# radio103.net
KiCad netlist of a schematic drawn in EAGLE
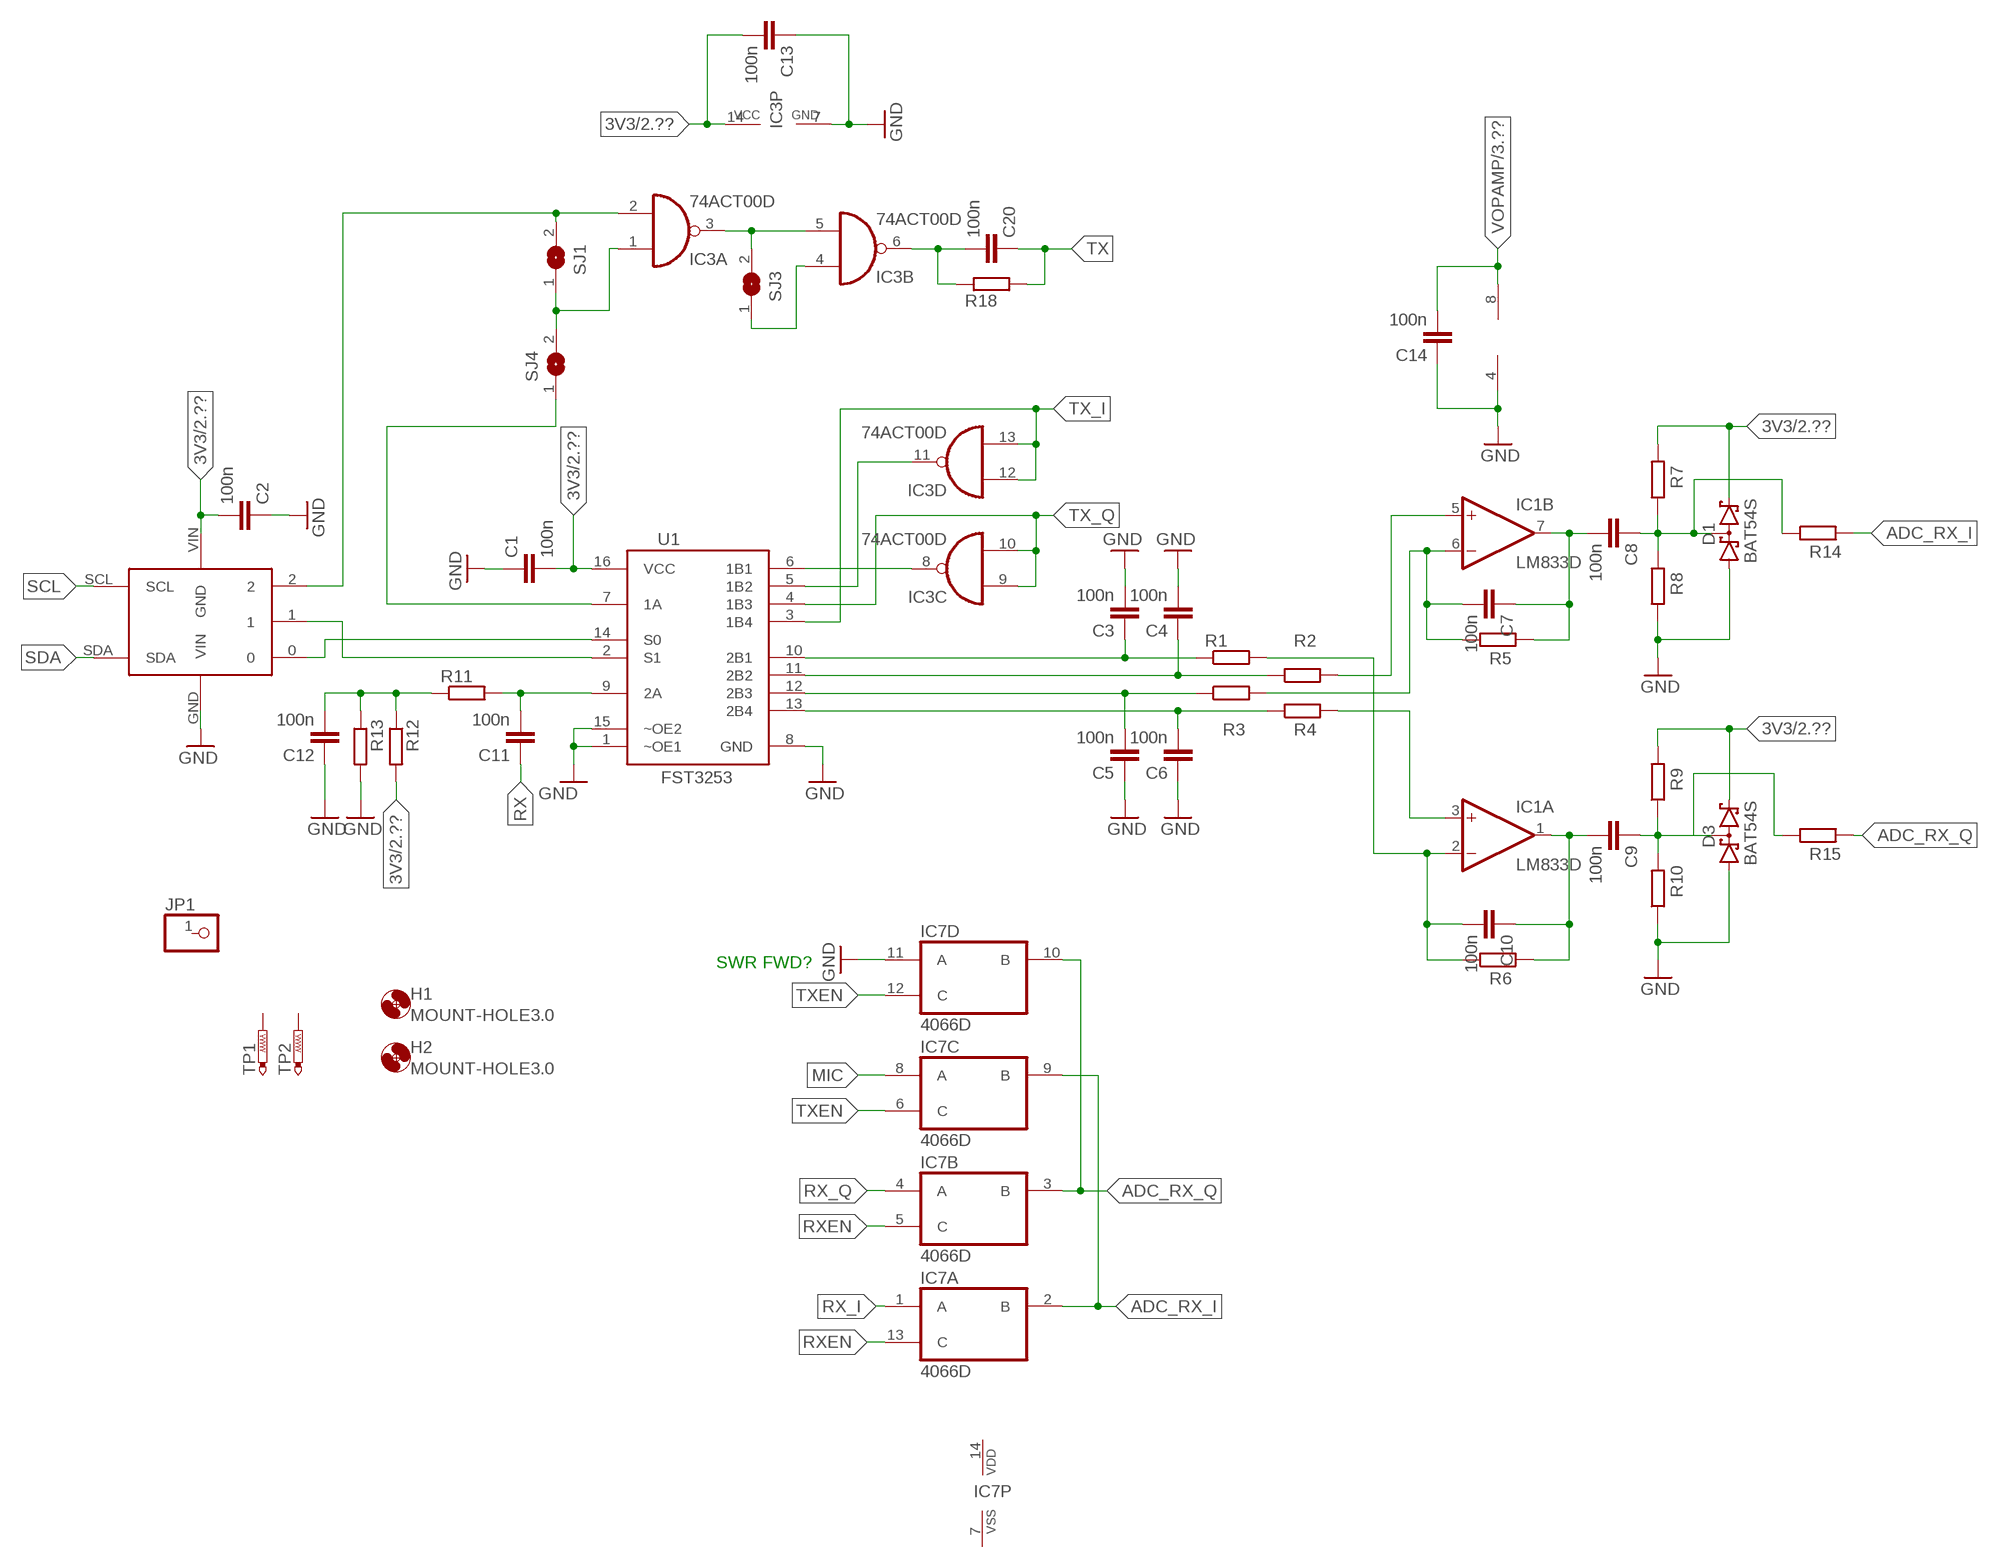
[diagram p0: schematic, sheet 1]
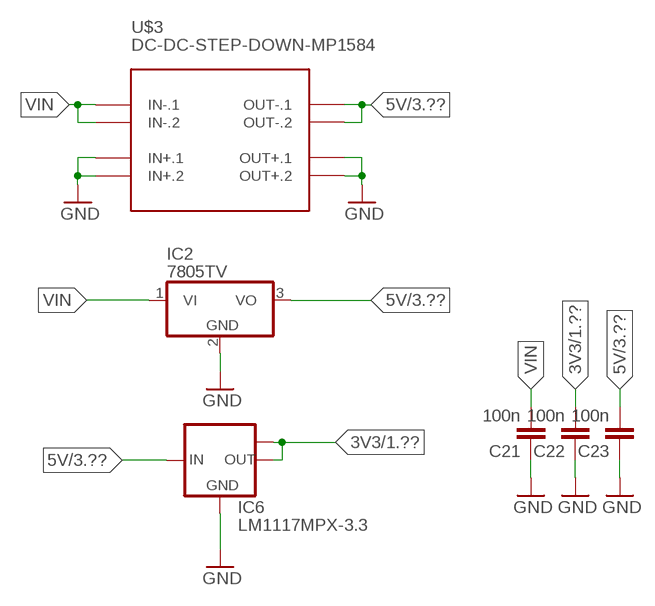
[diagram p1: schematic, sheet 2]
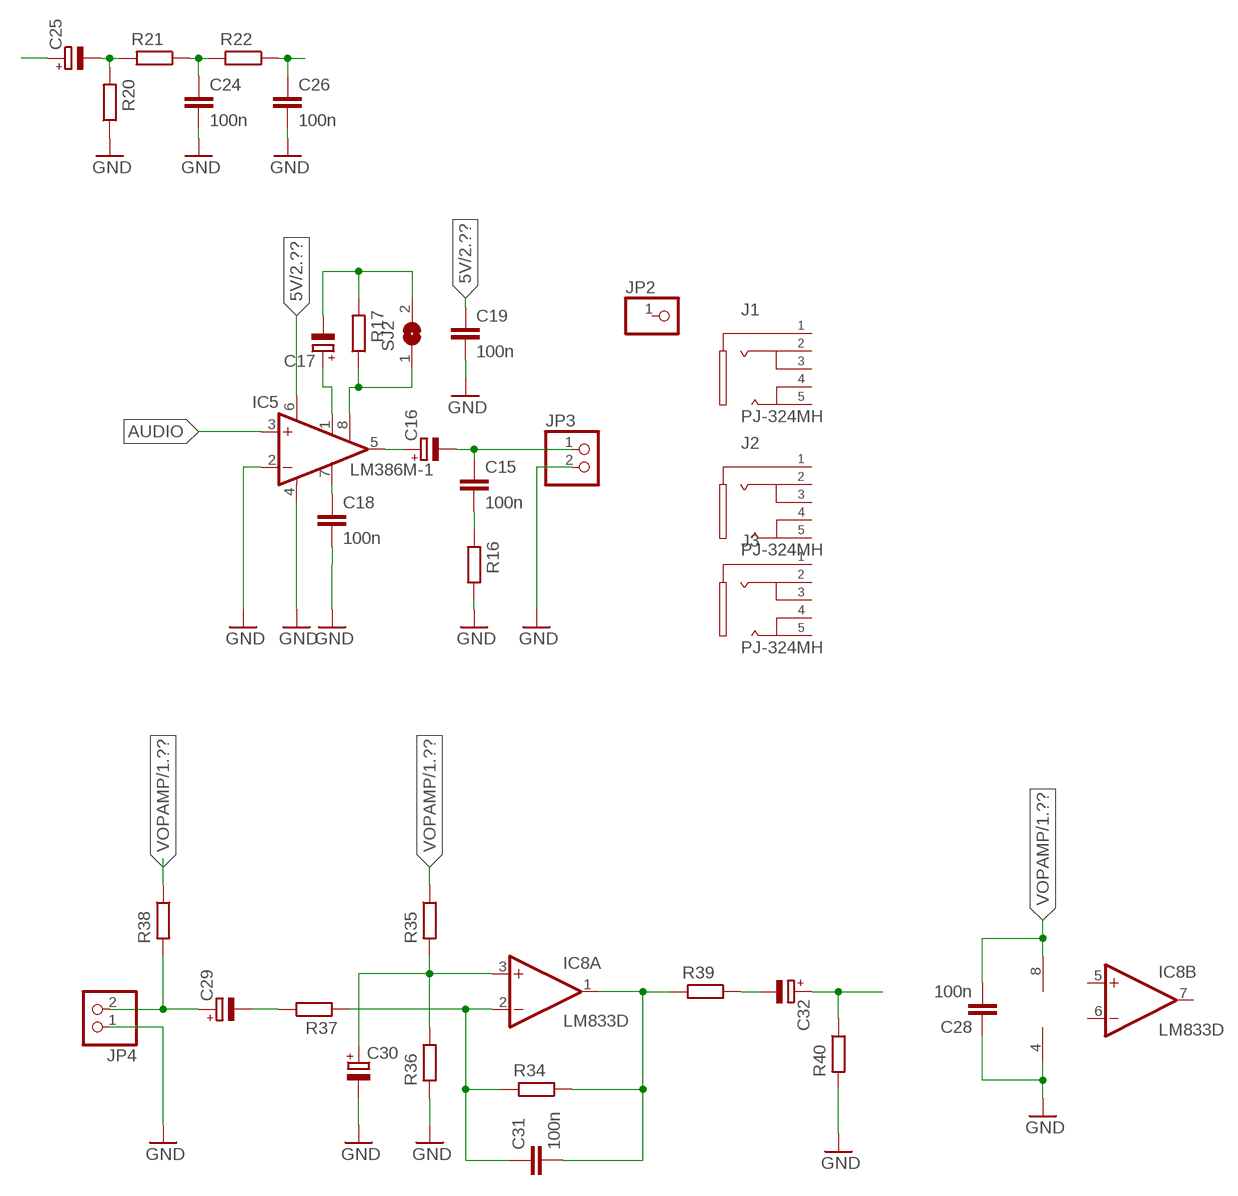
[diagram p2: schematic, sheet 3]

(export (version "E")
  (design (tool "Eeschema 10.0.6"))
  (components
    (comp (ref "C15")
      (value "100n")
      (footprint "eagle-import:C0805K")
      (libsource (lib "eagle-import") (part "C-EUC0805K"))
    )
    (comp (ref "C16")
      (value "CPOL-EUE2,5-6E")
      (footprint "eagle-import:E2,5-6E")
      (libsource (lib "eagle-import") (part "CPOL-EUE2,5-6E"))
    )
    (comp (ref "C17")
      (value "CPOL-EUE2,5-6E")
      (footprint "eagle-import:E2,5-6E")
      (libsource (lib "eagle-import") (part "CPOL-EUE2,5-6E"))
    )
    (comp (ref "C18")
      (value "100n")
      (footprint "eagle-import:C0805K")
      (libsource (lib "eagle-import") (part "C-EUC0805K"))
    )
    (comp (ref "C19")
      (value "100n")
      (footprint "eagle-import:C0805K")
      (libsource (lib "eagle-import") (part "C-EUC0805K"))
    )
    (comp (ref "C24")
      (value "100n")
      (footprint "eagle-import:C0805K")
      (libsource (lib "eagle-import") (part "C-EUC0805K"))
    )
    (comp (ref "C25")
      (value "CPOL-EUE2,5-6E")
      (footprint "eagle-import:E2,5-6E")
      (libsource (lib "eagle-import") (part "CPOL-EUE2,5-6E"))
    )
    (comp (ref "C26")
      (value "100n")
      (footprint "eagle-import:C0805K")
      (libsource (lib "eagle-import") (part "C-EUC0805K"))
    )
    (comp (ref "C28")
      (value "100n")
      (footprint "eagle-import:C0805K")
      (libsource (lib "eagle-import") (part "C-EUC0805K"))
    )
    (comp (ref "C29")
      (value "CPOL-EUE2,5-6E")
      (footprint "eagle-import:E2,5-6E")
      (libsource (lib "eagle-import") (part "CPOL-EUE2,5-6E"))
    )
    (comp (ref "C30")
      (value "CPOL-EUE2,5-6E")
      (footprint "eagle-import:E2,5-6E")
      (libsource (lib "eagle-import") (part "CPOL-EUE2,5-6E"))
    )
    (comp (ref "C31")
      (value "100n")
      (footprint "eagle-import:C0805K")
      (libsource (lib "eagle-import") (part "C-EUC0805K"))
    )
    (comp (ref "C32")
      (value "CPOL-EUE2,5-6E")
      (footprint "eagle-import:E2,5-6E")
      (libsource (lib "eagle-import") (part "CPOL-EUE2,5-6E"))
    )
    (comp (ref "IC5")
      (value "LM386M-1")
      (footprint "eagle-import:SO08")
      (libsource (lib "eagle-import") (part "LM386?-M1"))
    )
    (comp (ref "IC8")
      (value "LM833D")
      (footprint "eagle-import:SO08")
      (libsource (lib "eagle-import") (part "LM833D"))
    )
    (comp (ref "J1")
      (value "PJ-324MH")
      (footprint "eagle-import:PJ-324MH")
      (libsource (lib "eagle-import") (part "PJ-324MH"))
    )
    (comp (ref "J2")
      (value "PJ-324MH")
      (footprint "eagle-import:PJ-324MH")
      (libsource (lib "eagle-import") (part "PJ-324MH"))
    )
    (comp (ref "J3")
      (value "PJ-324MH")
      (footprint "eagle-import:PJ-324MH")
      (libsource (lib "eagle-import") (part "PJ-324MH"))
    )
    (comp (ref "JP2")
      (value "PINHD-1X1")
      (footprint "eagle-import:1X01")
      (libsource (lib "eagle-import") (part "PINHD-1X1"))
    )
    (comp (ref "JP3")
      (value "PINHD-1X2")
      (footprint "eagle-import:1X02")
      (libsource (lib "eagle-import") (part "PINHD-1X2"))
    )
    (comp (ref "JP4")
      (value "PINHD-1X2")
      (footprint "eagle-import:1X02")
      (libsource (lib "eagle-import") (part "PINHD-1X2"))
    )
    (comp (ref "R16")
      (value "R-EU_R0805")
      (footprint "eagle-import:R0805")
      (libsource (lib "eagle-import") (part "R-EU_R0805"))
    )
    (comp (ref "R17")
      (value "R-EU_R0805")
      (footprint "eagle-import:R0805")
      (libsource (lib "eagle-import") (part "R-EU_R0805"))
    )
    (comp (ref "R20")
      (value "R-EU_R0805")
      (footprint "eagle-import:R0805")
      (libsource (lib "eagle-import") (part "R-EU_R0805"))
    )
    (comp (ref "R21")
      (value "R-EU_R0805")
      (footprint "eagle-import:R0805")
      (libsource (lib "eagle-import") (part "R-EU_R0805"))
    )
    (comp (ref "R22")
      (value "R-EU_R0805")
      (footprint "eagle-import:R0805")
      (libsource (lib "eagle-import") (part "R-EU_R0805"))
    )
    (comp (ref "R34")
      (value "R-EU_R0805")
      (footprint "eagle-import:R0805")
      (libsource (lib "eagle-import") (part "R-EU_R0805"))
    )
    (comp (ref "R35")
      (value "R-EU_R0805")
      (footprint "eagle-import:R0805")
      (libsource (lib "eagle-import") (part "R-EU_R0805"))
    )
    (comp (ref "R36")
      (value "R-EU_R0805")
      (footprint "eagle-import:R0805")
      (libsource (lib "eagle-import") (part "R-EU_R0805"))
    )
    (comp (ref "R37")
      (value "R-EU_R0805")
      (footprint "eagle-import:R0805")
      (libsource (lib "eagle-import") (part "R-EU_R0805"))
    )
    (comp (ref "R38")
      (value "R-EU_R0805")
      (footprint "eagle-import:R0805")
      (libsource (lib "eagle-import") (part "R-EU_R0805"))
    )
    (comp (ref "R39")
      (value "R-EU_R0805")
      (footprint "eagle-import:R0805")
      (libsource (lib "eagle-import") (part "R-EU_R0805"))
    )
    (comp (ref "R40")
      (value "R-EU_R0805")
      (footprint "eagle-import:R0805")
      (libsource (lib "eagle-import") (part "R-EU_R0805"))
    )
    (comp (ref "SJ2") (value "SJ") (footprint "eagle-import:SJ") (libsource (lib "eagle-import") (part "SJ")))
    (comp (ref "C21")
      (value "100n")
      (footprint "eagle-import:C0805K")
      (libsource (lib "eagle-import") (part "C-EUC0805K"))
    )
    (comp (ref "C22")
      (value "100n")
      (footprint "eagle-import:C0805K")
      (libsource (lib "eagle-import") (part "C-EUC0805K"))
    )
    (comp (ref "C23")
      (value "100n")
      (footprint "eagle-import:C0805K")
      (libsource (lib "eagle-import") (part "C-EUC0805K"))
    )
    (comp (ref "IC2")
      (value "7805TV")
      (footprint "eagle-import:TO220V")
      (libsource (lib "eagle-import") (part "78TV05"))
    )
    (comp (ref "IC6")
      (value "LM1117MPX-3.3")
      (footprint "eagle-import:SOT223")
      (libsource (lib "eagle-import") (part "LM1117MPX-3.3"))
    )
    (comp (ref "U$3")
      (value "DC-DC-STEP-DOWN-MP1584")
      (footprint "eagle-import:DC-DC-STEP-DOWN-MP1584")
      (libsource (lib "eagle-import") (part "DC-DC-STEP-DOWN-MP1584"))
    )
    (comp (ref "C1")
      (value "100n")
      (footprint "eagle-import:C0805K")
      (libsource (lib "eagle-import") (part "C-EUC0805K"))
    )
    (comp (ref "C2")
      (value "100n")
      (footprint "eagle-import:C0805K")
      (libsource (lib "eagle-import") (part "C-EUC0805K"))
    )
    (comp (ref "C3")
      (value "100n")
      (footprint "eagle-import:C0805K")
      (libsource (lib "eagle-import") (part "C-EUC0805K"))
    )
    (comp (ref "C4")
      (value "100n")
      (footprint "eagle-import:C0805K")
      (libsource (lib "eagle-import") (part "C-EUC0805K"))
    )
    (comp (ref "C5")
      (value "100n")
      (footprint "eagle-import:C0805K")
      (libsource (lib "eagle-import") (part "C-EUC0805K"))
    )
    (comp (ref "C6")
      (value "100n")
      (footprint "eagle-import:C0805K")
      (libsource (lib "eagle-import") (part "C-EUC0805K"))
    )
    (comp (ref "C7")
      (value "100n")
      (footprint "eagle-import:C0805K")
      (libsource (lib "eagle-import") (part "C-EUC0805K"))
    )
    (comp (ref "C8")
      (value "100n")
      (footprint "eagle-import:C0805K")
      (libsource (lib "eagle-import") (part "C-EUC0805K"))
    )
    (comp (ref "C9")
      (value "100n")
      (footprint "eagle-import:C0805K")
      (libsource (lib "eagle-import") (part "C-EUC0805K"))
    )
    (comp (ref "C10")
      (value "100n")
      (footprint "eagle-import:C0805K")
      (libsource (lib "eagle-import") (part "C-EUC0805K"))
    )
    (comp (ref "C11")
      (value "100n")
      (footprint "eagle-import:C0805K")
      (libsource (lib "eagle-import") (part "C-EUC0805K"))
    )
    (comp (ref "C12")
      (value "100n")
      (footprint "eagle-import:C0805K")
      (libsource (lib "eagle-import") (part "C-EUC0805K"))
    )
    (comp (ref "C13")
      (value "100n")
      (footprint "eagle-import:C0805K")
      (libsource (lib "eagle-import") (part "C-EUC0805K"))
    )
    (comp (ref "C14")
      (value "100n")
      (footprint "eagle-import:C0805K")
      (libsource (lib "eagle-import") (part "C-EUC0805K"))
    )
    (comp (ref "C20")
      (value "100n")
      (footprint "eagle-import:C0805K")
      (libsource (lib "eagle-import") (part "C-EUC0805K"))
    )
    (comp (ref "D1")
      (value "BAT54S")
      (footprint "eagle-import:SOT23")
      (libsource (lib "eagle-import") (part "BAT54S"))
    )
    (comp (ref "D3")
      (value "BAT54S")
      (footprint "eagle-import:SOT23")
      (libsource (lib "eagle-import") (part "BAT54S"))
    )
    (comp (ref "H1")
      (value "MOUNT-HOLE3.0")
      (footprint "eagle-import:3,0")
      (libsource (lib "eagle-import") (part "MOUNT-HOLE3.0"))
    )
    (comp (ref "H2")
      (value "MOUNT-HOLE3.0")
      (footprint "eagle-import:3,0")
      (libsource (lib "eagle-import") (part "MOUNT-HOLE3.0"))
    )
    (comp (ref "IC1")
      (value "LM833D")
      (footprint "eagle-import:SO08")
      (libsource (lib "eagle-import") (part "LM833D"))
    )
    (comp (ref "IC3")
      (value "74ACT00D")
      (footprint "eagle-import:SO14")
      (libsource (lib "eagle-import") (part "7400DACT"))
    )
    (comp (ref "IC7")
      (value "4066D")
      (footprint "eagle-import:SO14")
      (libsource (lib "eagle-import") (part "4066D"))
    )
    (comp (ref "JP1")
      (value "PINHD-1X1")
      (footprint "eagle-import:1X01")
      (libsource (lib "eagle-import") (part "PINHD-1X1"))
    )
    (comp (ref "R1")
      (value "R-EU_R0805")
      (footprint "eagle-import:R0805")
      (libsource (lib "eagle-import") (part "R-EU_R0805"))
    )
    (comp (ref "R2")
      (value "R-EU_R0805")
      (footprint "eagle-import:R0805")
      (libsource (lib "eagle-import") (part "R-EU_R0805"))
    )
    (comp (ref "R3")
      (value "R-EU_R0805")
      (footprint "eagle-import:R0805")
      (libsource (lib "eagle-import") (part "R-EU_R0805"))
    )
    (comp (ref "R4")
      (value "R-EU_R0805")
      (footprint "eagle-import:R0805")
      (libsource (lib "eagle-import") (part "R-EU_R0805"))
    )
    (comp (ref "R5")
      (value "R-EU_R0805")
      (footprint "eagle-import:R0805")
      (libsource (lib "eagle-import") (part "R-EU_R0805"))
    )
    (comp (ref "R6")
      (value "R-EU_R0805")
      (footprint "eagle-import:R0805")
      (libsource (lib "eagle-import") (part "R-EU_R0805"))
    )
    (comp (ref "R7")
      (value "R-EU_R0805")
      (footprint "eagle-import:R0805")
      (libsource (lib "eagle-import") (part "R-EU_R0805"))
    )
    (comp (ref "R8")
      (value "R-EU_R0805")
      (footprint "eagle-import:R0805")
      (libsource (lib "eagle-import") (part "R-EU_R0805"))
    )
    (comp (ref "R9")
      (value "R-EU_R0805")
      (footprint "eagle-import:R0805")
      (libsource (lib "eagle-import") (part "R-EU_R0805"))
    )
    (comp (ref "R10")
      (value "R-EU_R0805")
      (footprint "eagle-import:R0805")
      (libsource (lib "eagle-import") (part "R-EU_R0805"))
    )
    (comp (ref "R11")
      (value "R-EU_R0805")
      (footprint "eagle-import:R0805")
      (libsource (lib "eagle-import") (part "R-EU_R0805"))
    )
    (comp (ref "R12")
      (value "R-EU_R0805")
      (footprint "eagle-import:R0805")
      (libsource (lib "eagle-import") (part "R-EU_R0805"))
    )
    (comp (ref "R13")
      (value "R-EU_R0805")
      (footprint "eagle-import:R0805")
      (libsource (lib "eagle-import") (part "R-EU_R0805"))
    )
    (comp (ref "R14")
      (value "R-EU_R0805")
      (footprint "eagle-import:R0805")
      (libsource (lib "eagle-import") (part "R-EU_R0805"))
    )
    (comp (ref "R15")
      (value "R-EU_R0805")
      (footprint "eagle-import:R0805")
      (libsource (lib "eagle-import") (part "R-EU_R0805"))
    )
    (comp (ref "R18")
      (value "R-EU_R0805")
      (footprint "eagle-import:R0805")
      (libsource (lib "eagle-import") (part "R-EU_R0805"))
    )
    (comp (ref "SJ1") (value "SJ") (footprint "eagle-import:SJ") (libsource (lib "eagle-import") (part "SJ")))
    (comp (ref "SJ3") (value "SJ") (footprint "eagle-import:SJ") (libsource (lib "eagle-import") (part "SJ")))
    (comp (ref "SJ4") (value "SJ") (footprint "eagle-import:SJ") (libsource (lib "eagle-import") (part "SJ")))
    (comp (ref "TP1")
      (value "PTR1B2,54")
      (footprint "eagle-import:B2,54")
      (libsource (lib "eagle-import") (part "PTR1B2,54"))
    )
    (comp (ref "TP2")
      (value "PTR1B1,27")
      (footprint "eagle-import:B1,27")
      (libsource (lib "eagle-import") (part "PTR1B1,27"))
    )
    (comp (ref "U$2")
      (value "CJMCU-5351")
      (footprint "eagle-import:CJMCU-5351")
      (libsource (lib "eagle-import") (part "CJMCU-5351"))
    )
    (comp (ref "U1")
      (value "FST3253")
      (footprint "eagle-import:TSSOP16L")
      (libsource (lib "eagle-import") (part "FST3253"))
    )
  )
  (nets
    (net (code "1") (name "3V3") (class "Default")
      (node (ref "C1") (pin "2") (pinfunction "2_2") (pintype "passive"))
      (node (ref "C13") (pin "2") (pinfunction "2_2") (pintype "passive"))
      (node (ref "C2") (pin "2") (pinfunction "2_2") (pintype "passive"))
      (node (ref "C22") (pin "2") (pinfunction "2_2") (pintype "passive"))
      (node (ref "D1") (pin "2") (pinfunction "C2_2") (pintype "passive"))
      (node (ref "D3") (pin "2") (pinfunction "C2_2") (pintype "passive"))
      (node (ref "IC3") (pin "14") (pinfunction "VCC_14") (pintype "power_in"))
      (node (ref "IC6") (pin "2") (pinfunction "OUT_2") (pintype "passive"))
      (node (ref "IC6") (pin "TAB") (pinfunction "OUT1_TAB") (pintype "passive"))
      (node (ref "R12") (pin "2") (pinfunction "2_2") (pintype "passive"))
      (node (ref "R7") (pin "2") (pinfunction "2_2") (pintype "passive"))
      (node (ref "R9") (pin "2") (pinfunction "2_2") (pintype "passive"))
      (node (ref "U$2") (pin "VIN") (pinfunction "GND_VIN") (pintype "bidirectional"))
      (node (ref "U1") (pin "16") (pinfunction "VCC_16") (pintype "bidirectional"))
    )
    (net (code "2") (name "5V") (class "Default")
      (node (ref "C19") (pin "1") (pinfunction "1_1") (pintype "passive"))
      (node (ref "C23") (pin "2") (pinfunction "2_2") (pintype "passive"))
      (node (ref "IC2") (pin "3") (pinfunction "VO_3") (pintype "passive"))
      (node (ref "IC5") (pin "6") (pinfunction "VS_6") (pintype "power_in"))
      (node (ref "IC6") (pin "3") (pinfunction "IN_3") (pintype "input"))
      (node (ref "U$3") (pin "OUT-.1") (pinfunction "OUT-.1_OUT-.1") (pintype "bidirectional"))
      (node (ref "U$3") (pin "OUT-.2") (pinfunction "OUT-.2_OUT-.2") (pintype "bidirectional"))
    )
    (net (code "3") (name "ADC_RX_I") (class "Default")
      (node (ref "IC7") (pin "2") (pinfunction "B_2") (pintype "tri_state"))
      (node (ref "IC7") (pin "9") (pinfunction "B_9") (pintype "tri_state"))
      (node (ref "R14") (pin "2") (pinfunction "2_2") (pintype "passive"))
    )
    (net (code "4") (name "ADC_RX_Q") (class "Default")
      (node (ref "IC7") (pin "10") (pinfunction "B_10") (pintype "tri_state"))
      (node (ref "IC7") (pin "3") (pinfunction "B_3") (pintype "tri_state"))
      (node (ref "R15") (pin "2") (pinfunction "2_2") (pintype "passive"))
    )
    (net (code "5") (name "AUDIO") (class "Default")
      (node (ref "IC5") (pin "3") (pinfunction "+IN_3") (pintype "input"))
    )
    (net (code "6") (name "GND") (class "Default")
      (node (ref "C1") (pin "1") (pinfunction "1_1") (pintype "passive"))
      (node (ref "C12") (pin "1") (pinfunction "1_1") (pintype "passive"))
      (node (ref "C13") (pin "1") (pinfunction "1_1") (pintype "passive"))
      (node (ref "C14") (pin "1") (pinfunction "1_1") (pintype "passive"))
      (node (ref "C18") (pin "2") (pinfunction "2_2") (pintype "passive"))
      (node (ref "C19") (pin "2") (pinfunction "2_2") (pintype "passive"))
      (node (ref "C2") (pin "1") (pinfunction "1_1") (pintype "passive"))
      (node (ref "C21") (pin "1") (pinfunction "1_1") (pintype "passive"))
      (node (ref "C22") (pin "1") (pinfunction "1_1") (pintype "passive"))
      (node (ref "C23") (pin "1") (pinfunction "1_1") (pintype "passive"))
      (node (ref "C24") (pin "2") (pinfunction "2_2") (pintype "passive"))
      (node (ref "C26") (pin "2") (pinfunction "2_2") (pintype "passive"))
      (node (ref "C28") (pin "1") (pinfunction "1_1") (pintype "passive"))
      (node (ref "C3") (pin "2") (pinfunction "2_2") (pintype "passive"))
      (node (ref "C30") (pin "-") (pinfunction "-_-") (pintype "passive"))
      (node (ref "C4") (pin "2") (pinfunction "2_2") (pintype "passive"))
      (node (ref "C5") (pin "1") (pinfunction "1_1") (pintype "passive"))
      (node (ref "C6") (pin "1") (pinfunction "1_1") (pintype "passive"))
      (node (ref "D1") (pin "1") (pinfunction "A1_1") (pintype "passive"))
      (node (ref "D3") (pin "1") (pinfunction "A1_1") (pintype "passive"))
      (node (ref "IC1") (pin "4") (pinfunction "V-_4") (pintype "power_in"))
      (node (ref "IC2") (pin "2") (pinfunction "GND_2") (pintype "passive"))
      (node (ref "IC3") (pin "7") (pinfunction "GND_7") (pintype "power_in"))
      (node (ref "IC5") (pin "2") (pinfunction "-IN_2") (pintype "input"))
      (node (ref "IC5") (pin "4") (pinfunction "GND_4") (pintype "power_in"))
      (node (ref "IC6") (pin "1") (pinfunction "GND_1") (pintype "input"))
      (node (ref "IC7") (pin "11") (pinfunction "A_11") (pintype "tri_state"))
      (node (ref "IC8") (pin "4") (pinfunction "V-_4") (pintype "power_in"))
      (node (ref "JP3") (pin "2") (pinfunction "2_2") (pintype "passive"))
      (node (ref "JP4") (pin "1") (pinfunction "1_1") (pintype "passive"))
      (node (ref "R10") (pin "1") (pinfunction "1_1") (pintype "passive"))
      (node (ref "R13") (pin "2") (pinfunction "2_2") (pintype "passive"))
      (node (ref "R16") (pin "1") (pinfunction "1_1") (pintype "passive"))
      (node (ref "R20") (pin "1") (pinfunction "1_1") (pintype "passive"))
      (node (ref "R36") (pin "2") (pinfunction "2_2") (pintype "passive"))
      (node (ref "R40") (pin "2") (pinfunction "2_2") (pintype "passive"))
      (node (ref "R8") (pin "1") (pinfunction "1_1") (pintype "passive"))
      (node (ref "U$2") (pin "GND") (pinfunction "VIN_GND") (pintype "bidirectional"))
      (node (ref "U$3") (pin "IN+.1") (pinfunction "IN+.1_IN+.1") (pintype "bidirectional"))
      (node (ref "U$3") (pin "IN+.2") (pinfunction "IN+.2_IN+.2") (pintype "bidirectional"))
      (node (ref "U$3") (pin "OUT+.1") (pinfunction "OUT+.1_OUT+.1") (pintype "bidirectional"))
      (node (ref "U$3") (pin "OUT+.2") (pinfunction "OUT+.2_OUT+.2") (pintype "bidirectional"))
      (node (ref "U1") (pin "1") (pinfunction "~{OE1}_1") (pintype "bidirectional"))
      (node (ref "U1") (pin "15") (pinfunction "~{OE2}_15") (pintype "bidirectional"))
      (node (ref "U1") (pin "8") (pinfunction "GND_8") (pintype "bidirectional"))
    )
    (net (code "7") (name "MIC") (class "Default")
      (node (ref "IC7") (pin "8") (pinfunction "A_8") (pintype "tri_state"))
    )
    (net (code "8") (name "Net-(C12-Pad2)") (class "Default")
      (node (ref "C12") (pin "2") (pinfunction "2_2") (pintype "passive"))
      (node (ref "R11") (pin "1") (pinfunction "1_1") (pintype "passive"))
      (node (ref "R12") (pin "1") (pinfunction "1_1") (pintype "passive"))
      (node (ref "R13") (pin "1") (pinfunction "1_1") (pintype "passive"))
    )
    (net (code "9") (name "Net-(C15-Pad1)") (class "Default")
      (node (ref "C15") (pin "1") (pinfunction "1_1") (pintype "passive"))
      (node (ref "C16") (pin "-") (pinfunction "-_-") (pintype "passive"))
      (node (ref "JP3") (pin "1") (pinfunction "1_1") (pintype "passive"))
    )
    (net (code "10") (name "Net-(C15-Pad2)") (class "Default")
      (node (ref "C15") (pin "2") (pinfunction "2_2") (pintype "passive"))
      (node (ref "R16") (pin "2") (pinfunction "2_2") (pintype "passive"))
    )
    (net (code "11") (name "Net-(C17-Pad+)") (class "Default")
      (node (ref "C17") (pin "+") (pinfunction "+_+") (pintype "passive"))
      (node (ref "IC5") (pin "1") (pinfunction "GAIN_1") (pintype "passive"))
    )
    (net (code "12") (name "Net-(C17-Pad-)") (class "Default")
      (node (ref "C17") (pin "-") (pinfunction "-_-") (pintype "passive"))
      (node (ref "R17") (pin "2") (pinfunction "2_2") (pintype "passive"))
      (node (ref "SJ2") (pin "2") (pinfunction "2_2") (pintype "passive"))
    )
    (net (code "13") (name "Net-(C24-Pad1)") (class "Default")
      (node (ref "C24") (pin "1") (pinfunction "1_1") (pintype "passive"))
      (node (ref "R21") (pin "1") (pinfunction "1_1") (pintype "passive"))
      (node (ref "R22") (pin "2") (pinfunction "2_2") (pintype "passive"))
    )
    (net (code "14") (name "Net-(C25-Pad-)") (class "Default")
      (node (ref "C25") (pin "-") (pinfunction "-_-") (pintype "passive"))
      (node (ref "R20") (pin "2") (pinfunction "2_2") (pintype "passive"))
      (node (ref "R21") (pin "2") (pinfunction "2_2") (pintype "passive"))
    )
    (net (code "15") (name "Net-(C26-Pad1)") (class "Default")
      (node (ref "C26") (pin "1") (pinfunction "1_1") (pintype "passive"))
      (node (ref "R22") (pin "1") (pinfunction "1_1") (pintype "passive"))
    )
    (net (code "16") (name "Net-(C29-Pad+)") (class "Default")
      (node (ref "C29") (pin "+") (pinfunction "+_+") (pintype "passive"))
      (node (ref "JP4") (pin "2") (pinfunction "2_2") (pintype "passive"))
      (node (ref "R38") (pin "2") (pinfunction "2_2") (pintype "passive"))
    )
    (net (code "17") (name "Net-(C29-Pad-)") (class "Default")
      (node (ref "C29") (pin "-") (pinfunction "-_-") (pintype "passive"))
      (node (ref "R37") (pin "1") (pinfunction "1_1") (pintype "passive"))
    )
    (net (code "18") (name "Net-(C32-Pad+)") (class "Default")
      (node (ref "C32") (pin "+") (pinfunction "+_+") (pintype "passive"))
      (node (ref "R40") (pin "1") (pinfunction "1_1") (pintype "passive"))
    )
    (net (code "19") (name "Net-(C32-Pad-)") (class "Default")
      (node (ref "C32") (pin "-") (pinfunction "-_-") (pintype "passive"))
      (node (ref "R39") (pin "1") (pinfunction "1_1") (pintype "passive"))
    )
    (net (code "20") (name "Net-(D1-C1A2)") (class "Default")
      (node (ref "C8") (pin "1") (pinfunction "1_1") (pintype "passive"))
      (node (ref "D1") (pin "3") (pinfunction "C1A2_3") (pintype "passive"))
      (node (ref "R14") (pin "1") (pinfunction "1_1") (pintype "passive"))
      (node (ref "R7") (pin "1") (pinfunction "1_1") (pintype "passive"))
      (node (ref "R8") (pin "2") (pinfunction "2_2") (pintype "passive"))
    )
    (net (code "21") (name "Net-(D3-C1A2)") (class "Default")
      (node (ref "C9") (pin "1") (pinfunction "1_1") (pintype "passive"))
      (node (ref "D3") (pin "3") (pinfunction "C1A2_3") (pintype "passive"))
      (node (ref "R10") (pin "2") (pinfunction "2_2") (pintype "passive"))
      (node (ref "R15") (pin "1") (pinfunction "1_1") (pintype "passive"))
      (node (ref "R9") (pin "1") (pinfunction "1_1") (pintype "passive"))
    )
    (net (code "22") (name "Net-(IC1A-+IN)") (class "Default")
      (node (ref "IC1") (pin "3") (pinfunction "+IN_3") (pintype "input"))
      (node (ref "R4") (pin "2") (pinfunction "2_2") (pintype "passive"))
    )
    (net (code "23") (name "Net-(IC1A--IN)") (class "Default")
      (node (ref "C10") (pin "2") (pinfunction "2_2") (pintype "passive"))
      (node (ref "IC1") (pin "2") (pinfunction "-IN_2") (pintype "input"))
      (node (ref "R1") (pin "2") (pinfunction "2_2") (pintype "passive"))
      (node (ref "R6") (pin "1") (pinfunction "1_1") (pintype "passive"))
    )
    (net (code "24") (name "Net-(IC1A-OUT)") (class "Default")
      (node (ref "C10") (pin "1") (pinfunction "1_1") (pintype "passive"))
      (node (ref "C9") (pin "2") (pinfunction "2_2") (pintype "passive"))
      (node (ref "IC1") (pin "1") (pinfunction "OUT_1") (pintype "output"))
      (node (ref "R6") (pin "2") (pinfunction "2_2") (pintype "passive"))
    )
    (net (code "25") (name "Net-(IC1B-+IN)") (class "Default")
      (node (ref "IC1") (pin "5") (pinfunction "+IN_5") (pintype "input"))
      (node (ref "R2") (pin "2") (pinfunction "2_2") (pintype "passive"))
    )
    (net (code "26") (name "Net-(IC1B--IN)") (class "Default")
      (node (ref "C7") (pin "2") (pinfunction "2_2") (pintype "passive"))
      (node (ref "IC1") (pin "6") (pinfunction "-IN_6") (pintype "input"))
      (node (ref "R3") (pin "2") (pinfunction "2_2") (pintype "passive"))
      (node (ref "R5") (pin "1") (pinfunction "1_1") (pintype "passive"))
    )
    (net (code "27") (name "Net-(IC1B-OUT)") (class "Default")
      (node (ref "C7") (pin "1") (pinfunction "1_1") (pintype "passive"))
      (node (ref "C8") (pin "2") (pinfunction "2_2") (pintype "passive"))
      (node (ref "IC1") (pin "7") (pinfunction "OUT_7") (pintype "output"))
      (node (ref "R5") (pin "2") (pinfunction "2_2") (pintype "passive"))
    )
    (net (code "28") (name "Net-(IC3A-I0)") (class "Default")
      (node (ref "IC3") (pin "1") (pinfunction "I0_1") (pintype "input"))
      (node (ref "SJ1") (pin "1") (pinfunction "1_1") (pintype "passive"))
      (node (ref "SJ4") (pin "2") (pinfunction "2_2") (pintype "passive"))
    )
    (net (code "29") (name "Net-(IC3A-I1)") (class "Default")
      (node (ref "IC3") (pin "2") (pinfunction "I1_2") (pintype "input"))
      (node (ref "SJ1") (pin "2") (pinfunction "2_2") (pintype "passive"))
      (node (ref "U$2") (pin "2") (pinfunction "2_2") (pintype "bidirectional"))
    )
    (net (code "30") (name "Net-(IC3A-O)") (class "Default")
      (node (ref "IC3") (pin "3") (pinfunction "O_3") (pintype "output"))
      (node (ref "IC3") (pin "5") (pinfunction "I1_5") (pintype "input"))
      (node (ref "SJ3") (pin "2") (pinfunction "2_2") (pintype "passive"))
    )
    (net (code "31") (name "Net-(IC3B-I0)") (class "Default")
      (node (ref "IC3") (pin "4") (pinfunction "I0_4") (pintype "input"))
      (node (ref "SJ3") (pin "1") (pinfunction "1_1") (pintype "passive"))
    )
    (net (code "32") (name "Net-(IC3B-O)") (class "Default")
      (node (ref "C20") (pin "2") (pinfunction "2_2") (pintype "passive"))
      (node (ref "IC3") (pin "6") (pinfunction "O_6") (pintype "output"))
      (node (ref "R18") (pin "1") (pinfunction "1_1") (pintype "passive"))
    )
    (net (code "33") (name "Net-(IC3C-O)") (class "Default")
      (node (ref "IC3") (pin "8") (pinfunction "O_8") (pintype "output"))
      (node (ref "U1") (pin "6") (pinfunction "1B1_6") (pintype "bidirectional"))
    )
    (net (code "34") (name "Net-(IC3D-O)") (class "Default")
      (node (ref "IC3") (pin "11") (pinfunction "O_11") (pintype "output"))
      (node (ref "U1") (pin "5") (pinfunction "1B2_5") (pintype "bidirectional"))
    )
    (net (code "35") (name "Net-(IC5-BYPASS)") (class "Default")
      (node (ref "C18") (pin "1") (pinfunction "1_1") (pintype "passive"))
      (node (ref "IC5") (pin "7") (pinfunction "BYPASS_7") (pintype "passive"))
    )
    (net (code "36") (name "Net-(IC5-GAIN-Pad8)") (class "Default")
      (node (ref "IC5") (pin "8") (pinfunction "GAIN_8") (pintype "passive"))
      (node (ref "R17") (pin "1") (pinfunction "1_1") (pintype "passive"))
      (node (ref "SJ2") (pin "1") (pinfunction "1_1") (pintype "passive"))
    )
    (net (code "37") (name "Net-(IC5-OUT)") (class "Default")
      (node (ref "C16") (pin "+") (pinfunction "+_+") (pintype "passive"))
      (node (ref "IC5") (pin "5") (pinfunction "OUT_5") (pintype "output"))
    )
    (net (code "38") (name "Net-(IC8A-+IN)") (class "Default")
      (node (ref "C30") (pin "+") (pinfunction "+_+") (pintype "passive"))
      (node (ref "IC8") (pin "3") (pinfunction "+IN_3") (pintype "input"))
      (node (ref "R35") (pin "2") (pinfunction "2_2") (pintype "passive"))
      (node (ref "R36") (pin "1") (pinfunction "1_1") (pintype "passive"))
    )
    (net (code "39") (name "Net-(IC8A--IN)") (class "Default")
      (node (ref "C31") (pin "1") (pinfunction "1_1") (pintype "passive"))
      (node (ref "IC8") (pin "2") (pinfunction "-IN_2") (pintype "input"))
      (node (ref "R34") (pin "2") (pinfunction "2_2") (pintype "passive"))
      (node (ref "R37") (pin "2") (pinfunction "2_2") (pintype "passive"))
    )
    (net (code "40") (name "Net-(IC8A-OUT)") (class "Default")
      (node (ref "C31") (pin "2") (pinfunction "2_2") (pintype "passive"))
      (node (ref "IC8") (pin "1") (pinfunction "OUT_1") (pintype "output"))
      (node (ref "R34") (pin "1") (pinfunction "1_1") (pintype "passive"))
      (node (ref "R39") (pin "2") (pinfunction "2_2") (pintype "passive"))
    )
    (net (code "41") (name "Net-(U1-1A)") (class "Default")
      (node (ref "SJ4") (pin "1") (pinfunction "1_1") (pintype "passive"))
      (node (ref "U1") (pin "7") (pinfunction "1A_7") (pintype "bidirectional"))
    )
    (net (code "42") (name "Net-(U1-2A)") (class "Default")
      (node (ref "C11") (pin "2") (pinfunction "2_2") (pintype "passive"))
      (node (ref "R11") (pin "2") (pinfunction "2_2") (pintype "passive"))
      (node (ref "U1") (pin "9") (pinfunction "2A_9") (pintype "bidirectional"))
    )
    (net (code "43") (name "Net-(U1-2B1)") (class "Default")
      (node (ref "C3") (pin "1") (pinfunction "1_1") (pintype "passive"))
      (node (ref "R1") (pin "1") (pinfunction "1_1") (pintype "passive"))
      (node (ref "U1") (pin "10") (pinfunction "2B1_10") (pintype "bidirectional"))
    )
    (net (code "44") (name "Net-(U1-2B2)") (class "Default")
      (node (ref "C4") (pin "1") (pinfunction "1_1") (pintype "passive"))
      (node (ref "R2") (pin "1") (pinfunction "1_1") (pintype "passive"))
      (node (ref "U1") (pin "11") (pinfunction "2B2_11") (pintype "bidirectional"))
    )
    (net (code "45") (name "Net-(U1-2B3)") (class "Default")
      (node (ref "C5") (pin "2") (pinfunction "2_2") (pintype "passive"))
      (node (ref "R3") (pin "1") (pinfunction "1_1") (pintype "passive"))
      (node (ref "U1") (pin "12") (pinfunction "2B3_12") (pintype "bidirectional"))
    )
    (net (code "46") (name "Net-(U1-2B4)") (class "Default")
      (node (ref "C6") (pin "2") (pinfunction "2_2") (pintype "passive"))
      (node (ref "R4") (pin "1") (pinfunction "1_1") (pintype "passive"))
      (node (ref "U1") (pin "13") (pinfunction "2B4_13") (pintype "bidirectional"))
    )
    (net (code "47") (name "Net-(U1-S0)") (class "Default")
      (node (ref "U$2") (pin "0") (pinfunction "0_0") (pintype "bidirectional"))
      (node (ref "U1") (pin "14") (pinfunction "S0_14") (pintype "bidirectional"))
    )
    (net (code "48") (name "Net-(U1-S1)") (class "Default")
      (node (ref "U$2") (pin "1") (pinfunction "1_1") (pintype "bidirectional"))
      (node (ref "U1") (pin "2") (pinfunction "S1_2") (pintype "bidirectional"))
    )
    (net (code "49") (name "RX") (class "Default")
      (node (ref "C11") (pin "1") (pinfunction "1_1") (pintype "passive"))
    )
    (net (code "50") (name "RXEN") (class "Default")
      (node (ref "IC7") (pin "13") (pinfunction "C_13") (pintype "input"))
      (node (ref "IC7") (pin "5") (pinfunction "C_5") (pintype "input"))
    )
    (net (code "51") (name "RX_I") (class "Default")
      (node (ref "IC7") (pin "1") (pinfunction "A_1") (pintype "tri_state"))
    )
    (net (code "52") (name "RX_Q") (class "Default")
      (node (ref "IC7") (pin "4") (pinfunction "A_4") (pintype "tri_state"))
    )
    (net (code "53") (name "SCL") (class "Default")
      (node (ref "U$2") (pin "SCL") (pinfunction "SCL_SCL") (pintype "bidirectional"))
    )
    (net (code "54") (name "SDA") (class "Default")
      (node (ref "U$2") (pin "SDA") (pinfunction "SDA_SDA") (pintype "bidirectional"))
    )
    (net (code "55") (name "TX") (class "Default")
      (node (ref "C20") (pin "1") (pinfunction "1_1") (pintype "passive"))
      (node (ref "R18") (pin "2") (pinfunction "2_2") (pintype "passive"))
    )
    (net (code "56") (name "TXEN") (class "Default")
      (node (ref "IC7") (pin "12") (pinfunction "C_12") (pintype "input"))
      (node (ref "IC7") (pin "6") (pinfunction "C_6") (pintype "input"))
    )
    (net (code "57") (name "TX_I") (class "Default")
      (node (ref "IC3") (pin "12") (pinfunction "I0_12") (pintype "input"))
      (node (ref "IC3") (pin "13") (pinfunction "I1_13") (pintype "input"))
      (node (ref "U1") (pin "3") (pinfunction "1B4_3") (pintype "bidirectional"))
    )
    (net (code "58") (name "TX_Q") (class "Default")
      (node (ref "IC3") (pin "10") (pinfunction "I1_10") (pintype "input"))
      (node (ref "IC3") (pin "9") (pinfunction "I0_9") (pintype "input"))
      (node (ref "U1") (pin "4") (pinfunction "1B3_4") (pintype "bidirectional"))
    )
    (net (code "59") (name "VDD") (class "Default")
      (node (ref "IC7") (pin "14") (pinfunction "VDD_14") (pintype "power_in"))
    )
    (net (code "60") (name "VIN") (class "Default")
      (node (ref "C21") (pin "2") (pinfunction "2_2") (pintype "passive"))
      (node (ref "IC2") (pin "1") (pinfunction "VI_1") (pintype "input"))
      (node (ref "U$3") (pin "IN-.1") (pinfunction "IN-.1_IN-.1") (pintype "bidirectional"))
      (node (ref "U$3") (pin "IN-.2") (pinfunction "IN-.2_IN-.2") (pintype "bidirectional"))
    )
    (net (code "61") (name "VOPAMP") (class "Default")
      (node (ref "C14") (pin "2") (pinfunction "2_2") (pintype "passive"))
      (node (ref "C28") (pin "2") (pinfunction "2_2") (pintype "passive"))
      (node (ref "IC1") (pin "8") (pinfunction "V+_8") (pintype "power_in"))
      (node (ref "IC8") (pin "8") (pinfunction "V+_8") (pintype "power_in"))
      (node (ref "R35") (pin "1") (pinfunction "1_1") (pintype "passive"))
      (node (ref "R38") (pin "1") (pinfunction "1_1") (pintype "passive"))
    )
    (net (code "62") (name "VSS") (class "Default")
      (node (ref "IC7") (pin "7") (pinfunction "VSS_7") (pintype "power_in"))
    )
    (net (code "63") (name "unconnected-(C25-Pad+)") (class "Default")
      (node (ref "C25") (pin "+") (pinfunction "+_+") (pintype "passive"))
    )
    (net (code "64") (name "unconnected-(IC8B-+IN-Pad5)") (class "Default")
      (node (ref "IC8") (pin "5") (pinfunction "+IN_5") (pintype "input"))
    )
    (net (code "65") (name "unconnected-(IC8B--IN-Pad6)") (class "Default")
      (node (ref "IC8") (pin "6") (pinfunction "-IN_6") (pintype "input"))
    )
    (net (code "66") (name "unconnected-(IC8B-OUT-Pad7)") (class "Default")
      (node (ref "IC8") (pin "7") (pinfunction "OUT_7") (pintype "output"))
    )
    (net (code "67") (name "unconnected-(J1-Pad1)") (class "Default")
      (node (ref "J1") (pin "1") (pinfunction "1_1") (pintype "passive"))
    )
    (net (code "68") (name "unconnected-(J1-Pad2)") (class "Default")
      (node (ref "J1") (pin "2") (pinfunction "2_2") (pintype "passive"))
    )
    (net (code "69") (name "unconnected-(J1-Pad3)") (class "Default")
      (node (ref "J1") (pin "3") (pinfunction "3_3") (pintype "passive"))
    )
    (net (code "70") (name "unconnected-(J1-Pad4)") (class "Default")
      (node (ref "J1") (pin "4") (pinfunction "4_4") (pintype "passive"))
    )
    (net (code "71") (name "unconnected-(J1-Pad5)") (class "Default")
      (node (ref "J1") (pin "5") (pinfunction "5_5") (pintype "passive"))
    )
    (net (code "72") (name "unconnected-(J2-Pad1)") (class "Default")
      (node (ref "J2") (pin "1") (pinfunction "1_1") (pintype "passive"))
    )
    (net (code "73") (name "unconnected-(J2-Pad2)") (class "Default")
      (node (ref "J2") (pin "2") (pinfunction "2_2") (pintype "passive"))
    )
    (net (code "74") (name "unconnected-(J2-Pad3)") (class "Default")
      (node (ref "J2") (pin "3") (pinfunction "3_3") (pintype "passive"))
    )
    (net (code "75") (name "unconnected-(J2-Pad4)") (class "Default")
      (node (ref "J2") (pin "4") (pinfunction "4_4") (pintype "passive"))
    )
    (net (code "76") (name "unconnected-(J2-Pad5)") (class "Default")
      (node (ref "J2") (pin "5") (pinfunction "5_5") (pintype "passive"))
    )
    (net (code "77") (name "unconnected-(J3-Pad1)") (class "Default")
      (node (ref "J3") (pin "1") (pinfunction "1_1") (pintype "passive"))
    )
    (net (code "78") (name "unconnected-(J3-Pad2)") (class "Default")
      (node (ref "J3") (pin "2") (pinfunction "2_2") (pintype "passive"))
    )
    (net (code "79") (name "unconnected-(J3-Pad3)") (class "Default")
      (node (ref "J3") (pin "3") (pinfunction "3_3") (pintype "passive"))
    )
    (net (code "80") (name "unconnected-(J3-Pad4)") (class "Default")
      (node (ref "J3") (pin "4") (pinfunction "4_4") (pintype "passive"))
    )
    (net (code "81") (name "unconnected-(J3-Pad5)") (class "Default")
      (node (ref "J3") (pin "5") (pinfunction "5_5") (pintype "passive"))
    )
    (net (code "82") (name "unconnected-(JP1-Pad1)") (class "Default")
      (node (ref "JP1") (pin "1") (pinfunction "1_1") (pintype "passive"))
    )
    (net (code "83") (name "unconnected-(JP2-Pad1)") (class "Default")
      (node (ref "JP2") (pin "1") (pinfunction "1_1") (pintype "passive"))
    )
    (net (code "84") (name "unconnected-(TP1-PadTP)") (class "Default")
      (node (ref "TP1") (pin "TP") (pinfunction "TP_TP") (pintype "input"))
    )
    (net (code "85") (name "unconnected-(TP2-PadTP)") (class "Default")
      (node (ref "TP2") (pin "TP") (pinfunction "TP_TP") (pintype "input"))
    )
  )
)
